# 8_-IR_BACKLIGHT.net
KiCad netlist of a schematic drawn in Altium Designer
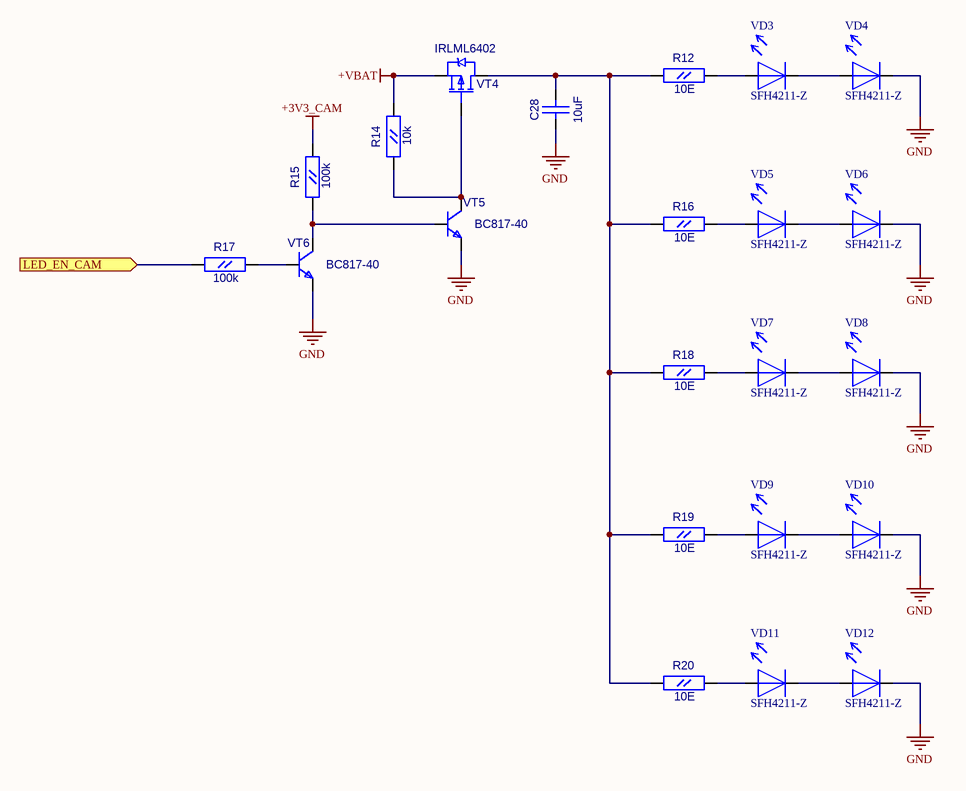
[diagram p0: [8]-IR_BACKLIGHT.SchDoc]

(export (version "E")
  (design (tool "Eeschema 10.0.6"))
  (components
    (comp (ref "C28")
      (value "10uF")
      (footprint "CC0805")
      (description "CC0805")
      (libsource (lib "fizik_lib") (part "CC0805"))
    )
    (comp (ref "R12")
      (value "10E")
      (footprint "RC0603")
      (description "RC0603")
      (libsource (lib "fizik_lib") (part "RC0603"))
    )
    (comp (ref "R14")
      (value "10k")
      (footprint "RC0603")
      (description "RC0603")
      (libsource (lib "fizik_lib") (part "RC0603"))
    )
    (comp (ref "R15")
      (value "100k")
      (footprint "RC0603")
      (description "RC0603")
      (libsource (lib "fizik_lib") (part "RC0603"))
    )
    (comp (ref "R16")
      (value "10E")
      (footprint "RC0603")
      (description "RC0603")
      (libsource (lib "fizik_lib") (part "RC0603"))
    )
    (comp (ref "R17")
      (value "100k")
      (footprint "RC0603")
      (description "RC0603")
      (libsource (lib "fizik_lib") (part "RC0603"))
    )
    (comp (ref "R18")
      (value "10E")
      (footprint "RC0603")
      (description "RC0603")
      (libsource (lib "fizik_lib") (part "RC0603"))
    )
    (comp (ref "R19")
      (value "10E")
      (footprint "RC0603")
      (description "RC0603")
      (libsource (lib "fizik_lib") (part "RC0603"))
    )
    (comp (ref "R20")
      (value "10E")
      (footprint "RC0603")
      (description "RC0603")
      (libsource (lib "fizik_lib") (part "RC0603"))
    )
    (comp (ref "VD3")
      (value "SFH4211-Z")
      (footprint "LED_3528")
      (libsource (lib "fizik_lib") (part "LED_3528"))
    )
    (comp (ref "VD4")
      (value "SFH4211-Z")
      (footprint "LED_3528")
      (libsource (lib "fizik_lib") (part "LED_3528"))
    )
    (comp (ref "VD5")
      (value "SFH4211-Z")
      (footprint "LED_3528")
      (libsource (lib "fizik_lib") (part "LED_3528"))
    )
    (comp (ref "VD6")
      (value "SFH4211-Z")
      (footprint "LED_3528")
      (libsource (lib "fizik_lib") (part "LED_3528"))
    )
    (comp (ref "VD7")
      (value "SFH4211-Z")
      (footprint "LED_3528")
      (libsource (lib "fizik_lib") (part "LED_3528"))
    )
    (comp (ref "VD8")
      (value "SFH4211-Z")
      (footprint "LED_3528")
      (libsource (lib "fizik_lib") (part "LED_3528"))
    )
    (comp (ref "VD9")
      (value "SFH4211-Z")
      (footprint "LED_3528")
      (libsource (lib "fizik_lib") (part "LED_3528"))
    )
    (comp (ref "VD10")
      (value "SFH4211-Z")
      (footprint "LED_3528")
      (libsource (lib "fizik_lib") (part "LED_3528"))
    )
    (comp (ref "VD11")
      (value "SFH4211-Z")
      (footprint "LED_3528")
      (libsource (lib "fizik_lib") (part "LED_3528"))
    )
    (comp (ref "VD12")
      (value "SFH4211-Z")
      (footprint "LED_3528")
      (libsource (lib "fizik_lib") (part "LED_3528"))
    )
    (comp (ref "VT4")
      (value "IRLML6402")
      (footprint "SOT-23(123)")
      (description "HEXFET Power MOSFET")
      (libsource (lib "fizik_lib") (part "IRLML6402"))
    )
    (comp (ref "VT5")
      (value "BC817-40")
      (footprint "SOT-23(123)")
      (description "NPN 500ma transistor")
      (libsource (lib "fizik_lib") (part "BC846BLT1"))
    )
    (comp (ref "VT6")
      (value "BC817-40")
      (footprint "SOT-23(123)")
      (description "NPN 500ma transistor")
      (libsource (lib "fizik_lib") (part "BC846BLT1"))
    )
  )
  (nets
    (net (code "1") (name "+3V3_CAM") (class "Default")
      (node (ref "R15") (pin "2") (pinfunction "B_2") (pintype "passive"))
    )
    (net (code "2") (name "+VBAT") (class "Default")
      (node (ref "R14") (pin "2") (pinfunction "B_2") (pintype "passive"))
      (node (ref "VT4") (pin "2") (pinfunction "S_2") (pintype "passive"))
    )
    (net (code "3") (name "/LED_EN_CAM") (class "Default")
      (node (ref "R17") (pin "1") (pinfunction "A_1") (pintype "passive"))
    )
    (net (code "4") (name "GND") (class "Default")
      (node (ref "C28") (pin "1") (pinfunction "A_1") (pintype "passive"))
      (node (ref "VD10") (pin "2") (pintype "passive"))
      (node (ref "VD12") (pin "2") (pintype "passive"))
      (node (ref "VD4") (pin "2") (pintype "passive"))
      (node (ref "VD6") (pin "2") (pintype "passive"))
      (node (ref "VD8") (pin "2") (pintype "passive"))
      (node (ref "VT5") (pin "2") (pinfunction "E_2") (pintype "passive"))
      (node (ref "VT6") (pin "2") (pinfunction "E_2") (pintype "passive"))
    )
    (net (code "5") (name "Net-(C28-B)") (class "Default")
      (node (ref "C28") (pin "2") (pinfunction "B_2") (pintype "passive"))
      (node (ref "R12") (pin "1") (pinfunction "A_1") (pintype "passive"))
      (node (ref "R16") (pin "1") (pinfunction "A_1") (pintype "passive"))
      (node (ref "R18") (pin "1") (pinfunction "A_1") (pintype "passive"))
      (node (ref "R19") (pin "1") (pinfunction "A_1") (pintype "passive"))
      (node (ref "R20") (pin "1") (pinfunction "A_1") (pintype "passive"))
      (node (ref "VT4") (pin "3") (pinfunction "D_3") (pintype "passive"))
    )
    (net (code "6") (name "Net-(R12-B)") (class "Default")
      (node (ref "R12") (pin "2") (pinfunction "B_2") (pintype "passive"))
      (node (ref "VD3") (pin "1") (pintype "passive"))
    )
    (net (code "7") (name "Net-(R14-A)") (class "Default")
      (node (ref "R14") (pin "1") (pinfunction "A_1") (pintype "passive"))
      (node (ref "VT4") (pin "1") (pinfunction "G_1") (pintype "passive"))
      (node (ref "VT5") (pin "3") (pinfunction "C_3") (pintype "passive"))
    )
    (net (code "8") (name "Net-(R15-A)") (class "Default")
      (node (ref "R15") (pin "1") (pinfunction "A_1") (pintype "passive"))
      (node (ref "VT5") (pin "1") (pinfunction "B_1") (pintype "passive"))
      (node (ref "VT6") (pin "3") (pinfunction "C_3") (pintype "passive"))
    )
    (net (code "9") (name "Net-(R16-B)") (class "Default")
      (node (ref "R16") (pin "2") (pinfunction "B_2") (pintype "passive"))
      (node (ref "VD5") (pin "1") (pintype "passive"))
    )
    (net (code "10") (name "Net-(R17-B)") (class "Default")
      (node (ref "R17") (pin "2") (pinfunction "B_2") (pintype "passive"))
      (node (ref "VT6") (pin "1") (pinfunction "B_1") (pintype "passive"))
    )
    (net (code "11") (name "Net-(R18-B)") (class "Default")
      (node (ref "R18") (pin "2") (pinfunction "B_2") (pintype "passive"))
      (node (ref "VD7") (pin "1") (pintype "passive"))
    )
    (net (code "12") (name "Net-(R19-B)") (class "Default")
      (node (ref "R19") (pin "2") (pinfunction "B_2") (pintype "passive"))
      (node (ref "VD9") (pin "1") (pintype "passive"))
    )
    (net (code "13") (name "Net-(R20-B)") (class "Default")
      (node (ref "R20") (pin "2") (pinfunction "B_2") (pintype "passive"))
      (node (ref "VD11") (pin "1") (pintype "passive"))
    )
    (net (code "14") (name "Net-(VD3-Pad2)") (class "Default")
      (node (ref "VD3") (pin "2") (pintype "passive"))
      (node (ref "VD4") (pin "1") (pintype "passive"))
    )
    (net (code "15") (name "Net-(VD5-Pad2)") (class "Default")
      (node (ref "VD5") (pin "2") (pintype "passive"))
      (node (ref "VD6") (pin "1") (pintype "passive"))
    )
    (net (code "16") (name "Net-(VD7-Pad2)") (class "Default")
      (node (ref "VD7") (pin "2") (pintype "passive"))
      (node (ref "VD8") (pin "1") (pintype "passive"))
    )
    (net (code "17") (name "Net-(VD10-Pad1)") (class "Default")
      (node (ref "VD10") (pin "1") (pintype "passive"))
      (node (ref "VD9") (pin "2") (pintype "passive"))
    )
    (net (code "18") (name "Net-(VD11-Pad2)") (class "Default")
      (node (ref "VD11") (pin "2") (pintype "passive"))
      (node (ref "VD12") (pin "1") (pintype "passive"))
    )
  )
)
